# BreaV6.net
KiCad netlist of a schematic drawn in EAGLE
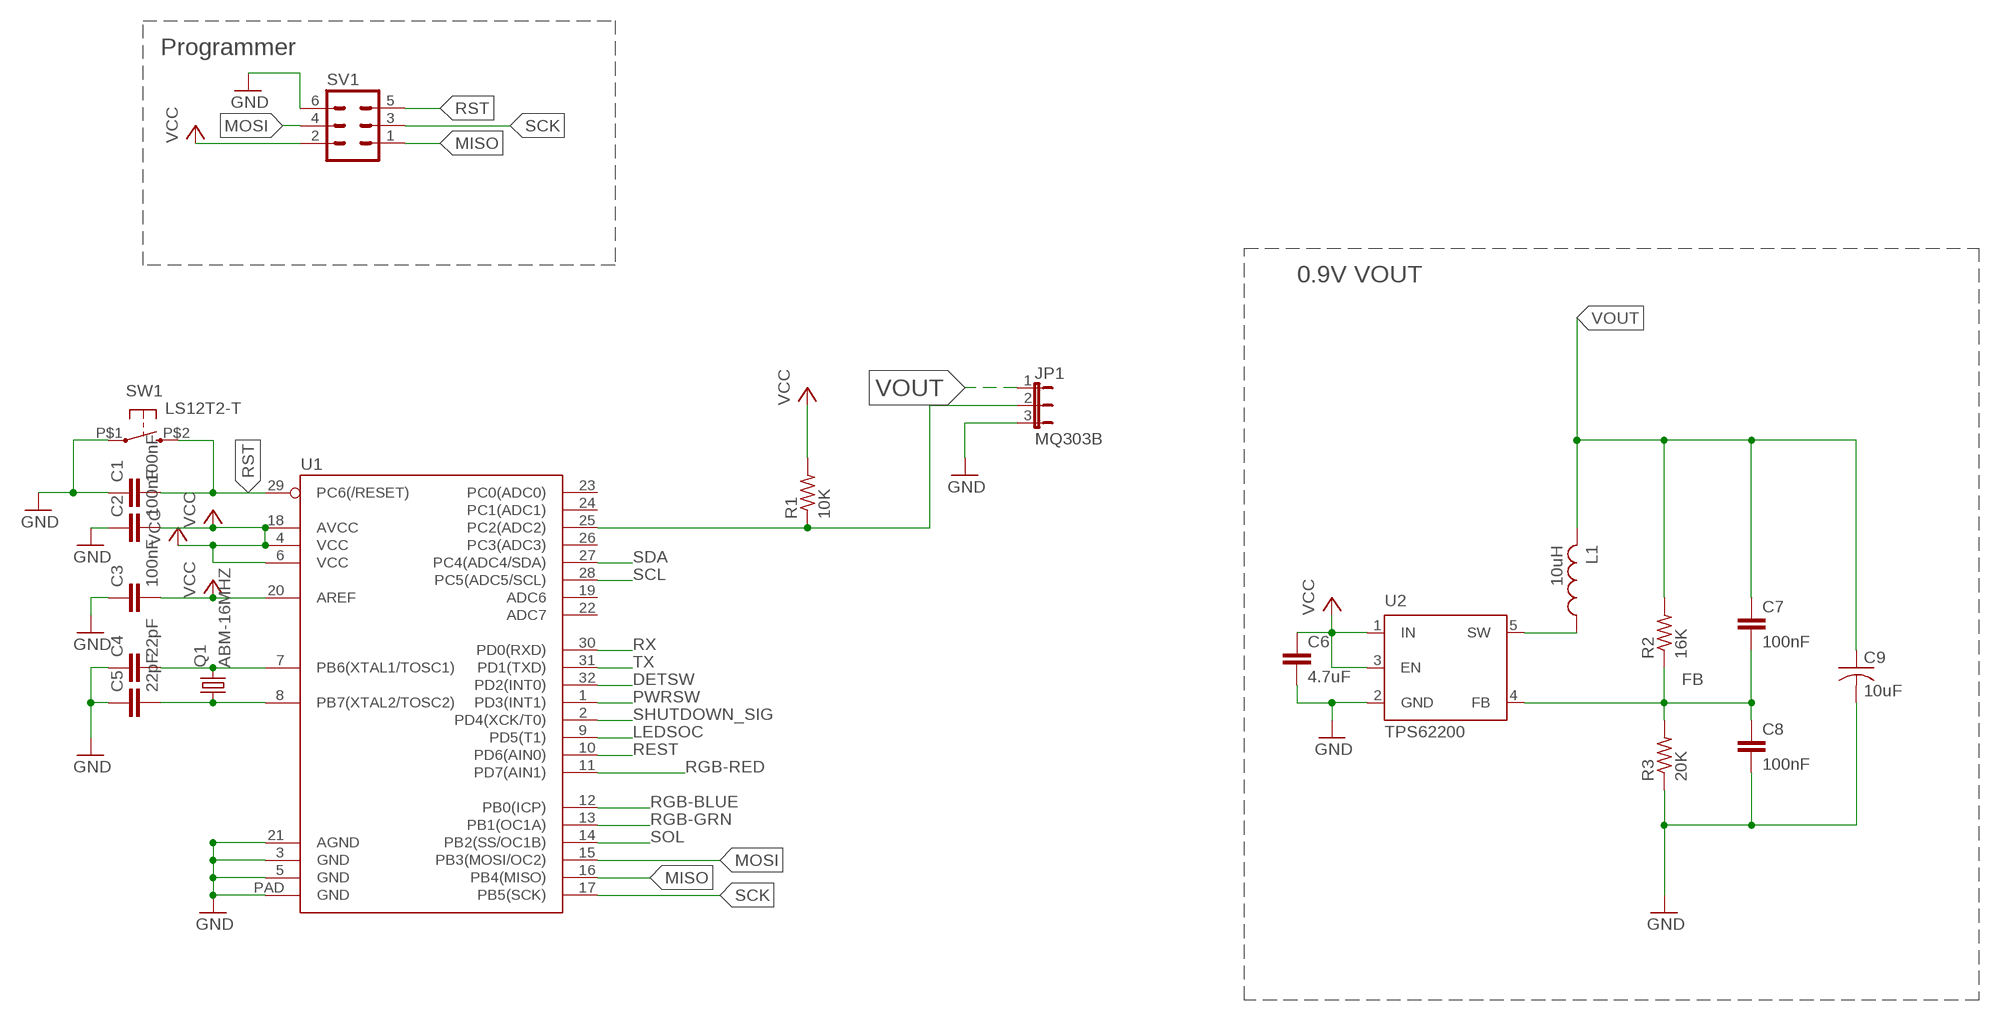
[diagram p0: schematic, sheet 1]
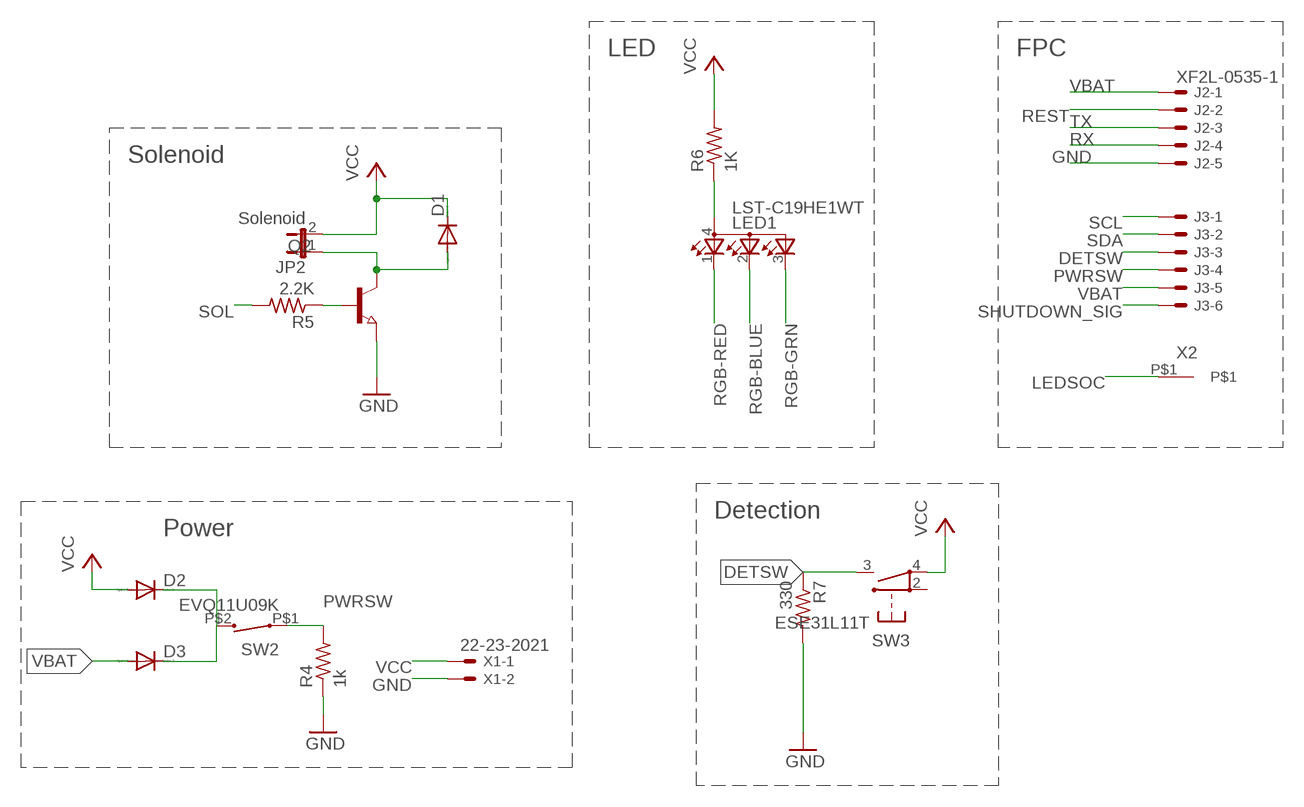
[diagram p1: schematic, sheet 2]

(export (version "E")
  (design (tool "Eeschema 10.0.6"))
  (components
    (comp (ref "C1")
      (value "100nF")
      (footprint "eagle-import:C0603")
      (libsource (lib "eagle-import") (part "C-EUC0603"))
    )
    (comp (ref "C2")
      (value "100nF")
      (footprint "eagle-import:C0603")
      (libsource (lib "eagle-import") (part "C-EUC0603"))
    )
    (comp (ref "C3")
      (value "100nF")
      (footprint "eagle-import:C0603")
      (libsource (lib "eagle-import") (part "C-EUC0603"))
    )
    (comp (ref "C4")
      (value "22pF")
      (footprint "eagle-import:C0603")
      (libsource (lib "eagle-import") (part "C-EUC0603"))
    )
    (comp (ref "C5")
      (value "22pF")
      (footprint "eagle-import:C0603")
      (libsource (lib "eagle-import") (part "C-EUC0603"))
    )
    (comp (ref "C6")
      (value "4.7uF")
      (footprint "eagle-import:C0402")
      (libsource (lib "eagle-import") (part "C-EUC0402"))
    )
    (comp (ref "C7")
      (value "100nF")
      (footprint "eagle-import:C0402")
      (libsource (lib "eagle-import") (part "C-EUC0402"))
    )
    (comp (ref "C8")
      (value "100nF")
      (footprint "eagle-import:C0402")
      (libsource (lib "eagle-import") (part "C-EUC0402"))
    )
    (comp (ref "C9")
      (value "10uF")
      (footprint "eagle-import:C0805K")
      (libsource (lib "eagle-import") (part "C-USC0805K"))
    )
    (comp (ref "JP1")
      (value "MQ303B")
      (footprint "eagle-import:JP2")
      (libsource (lib "eagle-import") (part "JP2E"))
    )
    (comp (ref "L1")
      (value "10uH")
      (footprint "eagle-import:L2825P")
      (libsource (lib "eagle-import") (part "L-USL2825P"))
    )
    (comp (ref "Q1")
      (value "ABM-16MHZ")
      (footprint "eagle-import:ABM-16MHZ")
      (libsource (lib "eagle-import") (part "ABM-16MHZ"))
    )
    (comp (ref "R1")
      (value "10K")
      (footprint "eagle-import:R0402")
      (libsource (lib "eagle-import") (part "R-US_R0402"))
    )
    (comp (ref "R2")
      (value "16K")
      (footprint "eagle-import:R0402")
      (libsource (lib "eagle-import") (part "R-US_R0402"))
    )
    (comp (ref "R3")
      (value "20K")
      (footprint "eagle-import:R0402")
      (libsource (lib "eagle-import") (part "R-US_R0402"))
    )
    (comp (ref "SV1")
      (value "MA03-2")
      (footprint "eagle-import:MA03-2")
      (libsource (lib "eagle-import") (part "MA03-2"))
    )
    (comp (ref "SW1")
      (value "LS12T2-T")
      (footprint "eagle-import:LS12T2-T")
      (libsource (lib "eagle-import") (part "LS12T2-T"))
    )
    (comp (ref "U1")
      (value "ATMEGA328P_MLFMLF32")
      (footprint "eagle-import:MLF32-PAD")
      (libsource (lib "eagle-import") (part "ATMEGA328P_MLFMLF32"))
    )
    (comp (ref "U2")
      (value "TPS62200")
      (footprint "eagle-import:TPS62200")
      (libsource (lib "eagle-import") (part "TPS62200"))
    )
    (comp (ref "D1")
      (value "DIODE-SOD123")
      (footprint "eagle-import:SOD123")
      (libsource (lib "eagle-import") (part "DIODE-SOD123"))
    )
    (comp (ref "D2")
      (value "DIODE-SOD523")
      (footprint "eagle-import:SOD523")
      (libsource (lib "eagle-import") (part "diode_210_DIODE-SOD523"))
    )
    (comp (ref "D3")
      (value "DIODE-SOD523")
      (footprint "eagle-import:SOD523")
      (libsource (lib "eagle-import") (part "diode_210_DIODE-SOD523"))
    )
    (comp (ref "J2")
      (value "XF2L-0535-1")
      (footprint "eagle-import:XF2L-0535-1")
      (libsource (lib "eagle-import") (part "XF2-05?35-1L"))
    )
    (comp (ref "J3")
      (value "XF2L-0635-1")
      (footprint "eagle-import:XF2L-0635-1")
      (libsource (lib "eagle-import") (part "XF2-06?35-1L"))
    )
    (comp (ref "JP2")
      (value "Solenoid")
      (footprint "eagle-import:JP1")
      (libsource (lib "eagle-import") (part "JP1E"))
    )
    (comp (ref "LED1")
      (value "LST-C19HE1WT")
      (footprint "eagle-import:LST-C19HE1WT")
      (libsource (lib "eagle-import") (part "LST-C19HE1WT"))
    )
    (comp (ref "Q2")
      (value "NPN-TRANSISTOR_SOT23")
      (footprint "eagle-import:SOT23")
      (libsource (lib "eagle-import") (part "NPN-TRANSISTOR_SOT23"))
    )
    (comp (ref "R4")
      (value "1k")
      (footprint "eagle-import:R0402")
      (libsource (lib "eagle-import") (part "R-US_R0402"))
    )
    (comp (ref "R5")
      (value "2.2K")
      (footprint "eagle-import:R0402")
      (libsource (lib "eagle-import") (part "R-US_R0402"))
    )
    (comp (ref "R6")
      (value "1K")
      (footprint "eagle-import:R0402")
      (libsource (lib "eagle-import") (part "R-US_R0402"))
    )
    (comp (ref "R7")
      (value "330")
      (footprint "eagle-import:R0402")
      (libsource (lib "eagle-import") (part "R-US_R0402"))
    )
    (comp (ref "SW2")
      (value "EVQ11U09K")
      (footprint "eagle-import:EVQ11U-09K")
      (libsource (lib "eagle-import") (part "EVQ11U09K"))
    )
    (comp (ref "SW3")
      (value "ESE31L11T")
      (footprint "eagle-import:SWITCH")
      (libsource (lib "eagle-import") (part "ESE31L11T"))
    )
    (comp (ref "X1")
      (value "22-23-2021")
      (footprint "eagle-import:22-23-2021")
      (fields (field (name "MF") "MOLEX"))
      (libsource (lib "eagle-import") (part "22-23-2021"))
    )
    (comp (ref "X2")
      (value "CON-1PINB")
      (footprint "eagle-import:CON-1PIN-B")
      (libsource (lib "eagle-import") (part "CON-1PINB"))
    )
  )
  (nets
    (net (code "1") (name "DETSW") (class "Default")
      (node (ref "J3") (pin "3") (pinfunction "MS_3") (pintype "passive"))
      (node (ref "R7") (pin "1") (pinfunction "1_1") (pintype "passive"))
      (node (ref "SW3") (pin "3") (pinfunction "1_3") (pintype "passive"))
      (node (ref "U1") (pin "32") (pinfunction "PD2(INT0)_32") (pintype "bidirectional"))
    )
    (net (code "2") (name "FB") (class "Default")
      (node (ref "C7") (pin "2") (pinfunction "2_2") (pintype "passive"))
      (node (ref "C8") (pin "1") (pinfunction "1_1") (pintype "passive"))
      (node (ref "R2") (pin "1") (pinfunction "1_1") (pintype "passive"))
      (node (ref "R3") (pin "2") (pinfunction "2_2") (pintype "passive"))
      (node (ref "U2") (pin "4") (pinfunction "FB_4") (pintype "passive"))
    )
    (net (code "3") (name "GND") (class "Default")
      (node (ref "C1") (pin "1") (pinfunction "1_1") (pintype "passive"))
      (node (ref "C2") (pin "1") (pinfunction "1_1") (pintype "passive"))
      (node (ref "C3") (pin "1") (pinfunction "1_1") (pintype "passive"))
      (node (ref "C4") (pin "1") (pinfunction "1_1") (pintype "passive"))
      (node (ref "C5") (pin "1") (pinfunction "1_1") (pintype "passive"))
      (node (ref "C6") (pin "2") (pinfunction "2_2") (pintype "passive"))
      (node (ref "C8") (pin "2") (pinfunction "2_2") (pintype "passive"))
      (node (ref "C9") (pin "2") (pinfunction "2_2") (pintype "passive"))
      (node (ref "J2") (pin "5") (pinfunction "MS_5") (pintype "passive"))
      (node (ref "JP1") (pin "3") (pinfunction "3_3") (pintype "passive"))
      (node (ref "Q2") (pin "2") (pinfunction "E_2") (pintype "passive"))
      (node (ref "R3") (pin "1") (pinfunction "1_1") (pintype "passive"))
      (node (ref "R4") (pin "1") (pinfunction "1_1") (pintype "passive"))
      (node (ref "R7") (pin "2") (pinfunction "2_2") (pintype "passive"))
      (node (ref "SV1") (pin "6") (pinfunction "MISO_6") (pintype "passive"))
      (node (ref "SW1") (pin "P$1") (pinfunction "S1_P$1") (pintype "passive"))
      (node (ref "U1") (pin "21") (pinfunction "AGND_21") (pintype "bidirectional"))
      (node (ref "U1") (pin "3") (pinfunction "GND_3") (pintype "bidirectional"))
      (node (ref "U1") (pin "5") (pinfunction "GND_5") (pintype "bidirectional"))
      (node (ref "U1") (pin "PAD") (pinfunction "GND_PAD") (pintype "bidirectional"))
      (node (ref "U2") (pin "2") (pinfunction "GND_2") (pintype "power_in"))
      (node (ref "X1") (pin "2") (pinfunction "S_2") (pintype "passive"))
    )
    (net (code "4") (name "LEDSOC") (class "Default")
      (node (ref "U1") (pin "9") (pinfunction "PD5(T1)_9") (pintype "bidirectional"))
      (node (ref "X2") (pin "P$1") (pinfunction "P$1_P$1") (pintype "bidirectional"))
    )
    (net (code "5") (name "MISO") (class "Default")
      (node (ref "SV1") (pin "1") (pinfunction "1_1") (pintype "passive"))
      (node (ref "U1") (pin "16") (pinfunction "PB4(MISO)_16") (pintype "bidirectional"))
    )
    (net (code "6") (name "MOSI") (class "Default")
      (node (ref "SV1") (pin "4") (pinfunction "4_4") (pintype "passive"))
      (node (ref "U1") (pin "15") (pinfunction "PB3(MOSI/OC2)_15") (pintype "bidirectional"))
    )
    (net (code "7") (name "Net-(LED1-A)") (class "Default")
      (node (ref "LED1") (pin "4") (pinfunction "A_4") (pintype "passive"))
      (node (ref "R6") (pin "1") (pinfunction "1_1") (pintype "passive"))
    )
    (net (code "8") (name "Net-(Q1-1)") (class "Default")
      (node (ref "C5") (pin "2") (pinfunction "2_2") (pintype "passive"))
      (node (ref "Q1") (pin "P$1") (pinfunction "1_P$1") (pintype "passive"))
      (node (ref "U1") (pin "8") (pinfunction "PB7(XTAL2/TOSC2)_8") (pintype "bidirectional"))
    )
    (net (code "9") (name "Net-(Q1-2)") (class "Default")
      (node (ref "C4") (pin "2") (pinfunction "2_2") (pintype "passive"))
      (node (ref "Q1") (pin "P$2") (pinfunction "2_P$2") (pintype "passive"))
      (node (ref "U1") (pin "7") (pinfunction "PB6(XTAL1/TOSC1)_7") (pintype "bidirectional"))
    )
    (net (code "10") (name "Net-(Q2-B)") (class "Default")
      (node (ref "Q2") (pin "1") (pinfunction "B_1") (pintype "passive"))
      (node (ref "R5") (pin "1") (pinfunction "1_1") (pintype "passive"))
    )
    (net (code "11") (name "Net-(Q2-C)") (class "Default")
      (node (ref "D1") (pin "A") (pinfunction "A_A") (pintype "passive"))
      (node (ref "JP2") (pin "1") (pinfunction "1_1") (pintype "passive"))
      (node (ref "Q2") (pin "3") (pinfunction "C_3") (pintype "passive"))
    )
    (net (code "12") (name "Net-(SW2-2)") (class "Default")
      (node (ref "D2") (pin "C") (pinfunction "C_C") (pintype "passive"))
      (node (ref "D3") (pin "C") (pinfunction "C_C") (pintype "passive"))
      (node (ref "SW2") (pin "P$2") (pinfunction "2_P$2") (pintype "passive"))
    )
    (net (code "13") (name "Net-(U1-PC2(ADC2))") (class "Default")
      (node (ref "JP1") (pin "2") (pinfunction "2_2") (pintype "passive"))
      (node (ref "R1") (pin "1") (pinfunction "1_1") (pintype "passive"))
      (node (ref "U1") (pin "25") (pinfunction "PC2(ADC2)_25") (pintype "bidirectional"))
    )
    (net (code "14") (name "Net-(U2-SW)") (class "Default")
      (node (ref "L1") (pin "1") (pinfunction "1_1") (pintype "passive"))
      (node (ref "U2") (pin "5") (pinfunction "SW_5") (pintype "passive"))
    )
    (net (code "15") (name "PWRSW") (class "Default")
      (node (ref "J3") (pin "4") (pinfunction "MS_4") (pintype "passive"))
      (node (ref "R4") (pin "2") (pinfunction "2_2") (pintype "passive"))
      (node (ref "SW2") (pin "P$1") (pinfunction "1_P$1") (pintype "passive"))
      (node (ref "U1") (pin "1") (pinfunction "PD3(INT1)_1") (pintype "bidirectional"))
    )
    (net (code "16") (name "REST") (class "Default")
      (node (ref "J2") (pin "2") (pinfunction "MS_2") (pintype "passive"))
      (node (ref "U1") (pin "10") (pinfunction "PD6(AIN0)_10") (pintype "bidirectional"))
    )
    (net (code "17") (name "RGB-BLUE") (class "Default")
      (node (ref "LED1") (pin "2") (pinfunction "CGREEN_2") (pintype "passive"))
      (node (ref "U1") (pin "12") (pinfunction "PB0(ICP)_12") (pintype "bidirectional"))
    )
    (net (code "18") (name "RGB-GRN") (class "Default")
      (node (ref "LED1") (pin "3") (pinfunction "CBLUE_3") (pintype "passive"))
      (node (ref "U1") (pin "13") (pinfunction "PB1(OC1A)_13") (pintype "bidirectional"))
    )
    (net (code "19") (name "RGB-RED") (class "Default")
      (node (ref "LED1") (pin "1") (pinfunction "CRED_1") (pintype "passive"))
      (node (ref "U1") (pin "11") (pinfunction "PD7(AIN1)_11") (pintype "bidirectional"))
    )
    (net (code "20") (name "RST") (class "Default")
      (node (ref "C1") (pin "2") (pinfunction "2_2") (pintype "passive"))
      (node (ref "SV1") (pin "5") (pinfunction "VTG_5") (pintype "passive"))
      (node (ref "SW1") (pin "P$2") (pinfunction "S2_P$2") (pintype "passive"))
      (node (ref "U1") (pin "29") (pinfunction "PC6(/RESET)_29") (pintype "bidirectional"))
    )
    (net (code "21") (name "RX") (class "Default")
      (node (ref "J2") (pin "4") (pinfunction "MS_4") (pintype "passive"))
      (node (ref "U1") (pin "30") (pinfunction "PD0(RXD)_30") (pintype "bidirectional"))
    )
    (net (code "22") (name "SCK") (class "Default")
      (node (ref "SV1") (pin "3") (pinfunction "3_3") (pintype "passive"))
      (node (ref "U1") (pin "17") (pinfunction "PB5(SCK)_17") (pintype "bidirectional"))
    )
    (net (code "23") (name "SCL") (class "Default")
      (node (ref "J3") (pin "1") (pinfunction "MS_1") (pintype "passive"))
      (node (ref "U1") (pin "28") (pinfunction "PC5(ADC5/SCL)_28") (pintype "bidirectional"))
    )
    (net (code "24") (name "SDA") (class "Default")
      (node (ref "J3") (pin "2") (pinfunction "MS_2") (pintype "passive"))
      (node (ref "U1") (pin "27") (pinfunction "PC4(ADC4/SDA)_27") (pintype "bidirectional"))
    )
    (net (code "25") (name "SHUTDOWN_SIG") (class "Default")
      (node (ref "J3") (pin "6") (pinfunction "MS_6") (pintype "passive"))
      (node (ref "U1") (pin "2") (pinfunction "PD4(XCK/T0)_2") (pintype "bidirectional"))
    )
    (net (code "26") (name "SOL") (class "Default")
      (node (ref "R5") (pin "2") (pinfunction "2_2") (pintype "passive"))
      (node (ref "U1") (pin "14") (pinfunction "PB2(SS/OC1B)_14") (pintype "bidirectional"))
    )
    (net (code "27") (name "TX") (class "Default")
      (node (ref "J2") (pin "3") (pinfunction "MS_3") (pintype "passive"))
      (node (ref "U1") (pin "31") (pinfunction "PD1(TXD)_31") (pintype "bidirectional"))
    )
    (net (code "28") (name "VBAT") (class "Default")
      (node (ref "D3") (pin "A") (pinfunction "A_A") (pintype "passive"))
      (node (ref "J2") (pin "1") (pinfunction "MSV_1") (pintype "passive"))
      (node (ref "J3") (pin "5") (pinfunction "MS_5") (pintype "passive"))
    )
    (net (code "29") (name "VCC") (class "Default")
      (node (ref "C2") (pin "2") (pinfunction "2_2") (pintype "passive"))
      (node (ref "C3") (pin "2") (pinfunction "2_2") (pintype "passive"))
      (node (ref "C6") (pin "1") (pinfunction "1_1") (pintype "passive"))
      (node (ref "D1") (pin "C") (pinfunction "C_C") (pintype "passive"))
      (node (ref "D2") (pin "A") (pinfunction "A_A") (pintype "passive"))
      (node (ref "JP2") (pin "2") (pinfunction "2_2") (pintype "passive"))
      (node (ref "R1") (pin "2") (pinfunction "2_2") (pintype "passive"))
      (node (ref "R6") (pin "2") (pinfunction "2_2") (pintype "passive"))
      (node (ref "SV1") (pin "2") (pinfunction "2_2") (pintype "passive"))
      (node (ref "SW3") (pin "4") (pinfunction "C3_4") (pintype "passive"))
      (node (ref "U1") (pin "18") (pinfunction "AVCC_18") (pintype "bidirectional"))
      (node (ref "U1") (pin "20") (pinfunction "AREF_20") (pintype "bidirectional"))
      (node (ref "U1") (pin "4") (pinfunction "VCC_4") (pintype "bidirectional"))
      (node (ref "U1") (pin "6") (pinfunction "VCC_6") (pintype "bidirectional"))
      (node (ref "U2") (pin "1") (pinfunction "IN_1") (pintype "input"))
      (node (ref "U2") (pin "3") (pinfunction "EN_3") (pintype "input"))
      (node (ref "X1") (pin "1") (pinfunction "S_1") (pintype "passive"))
    )
    (net (code "30") (name "VOUT") (class "Default")
      (node (ref "C7") (pin "1") (pinfunction "1_1") (pintype "passive"))
      (node (ref "C9") (pin "1") (pinfunction "1_1") (pintype "passive"))
      (node (ref "JP1") (pin "1") (pinfunction "1_1") (pintype "passive"))
      (node (ref "L1") (pin "2") (pinfunction "2_2") (pintype "passive"))
      (node (ref "R2") (pin "2") (pinfunction "2_2") (pintype "passive"))
    )
    (net (code "31") (name "unconnected-(SW3-C2-Pad2)") (class "Default")
      (node (ref "SW3") (pin "2") (pinfunction "C2_2") (pintype "passive"))
    )
    (net (code "32") (name "unconnected-(U1-ADC6-Pad19)") (class "Default")
      (node (ref "U1") (pin "19") (pinfunction "ADC6_19") (pintype "bidirectional"))
    )
    (net (code "33") (name "unconnected-(U1-ADC7-Pad22)") (class "Default")
      (node (ref "U1") (pin "22") (pinfunction "ADC7_22") (pintype "bidirectional"))
    )
    (net (code "34") (name "unconnected-(U1-PC0(ADC0)-Pad23)") (class "Default")
      (node (ref "U1") (pin "23") (pinfunction "PC0(ADC0)_23") (pintype "bidirectional"))
    )
    (net (code "35") (name "unconnected-(U1-PC1(ADC1)-Pad24)") (class "Default")
      (node (ref "U1") (pin "24") (pinfunction "PC1(ADC1)_24") (pintype "bidirectional"))
    )
    (net (code "36") (name "unconnected-(U1-PC3(ADC3)-Pad26)") (class "Default")
      (node (ref "U1") (pin "26") (pinfunction "PC3(ADC3)_26") (pintype "bidirectional"))
    )
  )
)
